# DRV10975_3-ph_Sensorless_BLDC_Motor_Driv.net
KiCad netlist of a schematic drawn in Altium Designer
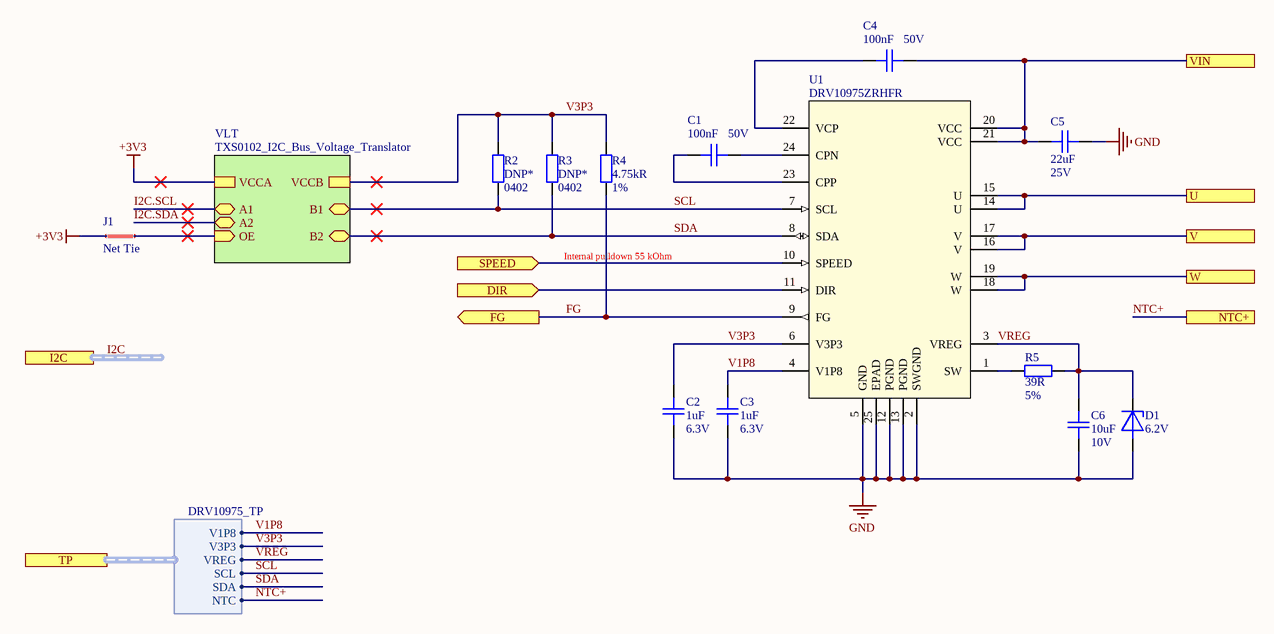
[diagram p0: DRV10975 3-ph Sensorless BLDC Motor Driver.SchDoc]

(export (version "E")
  (design (tool "Eeschema 10.0.6"))
  (components
    (comp (ref "C1")
      (value "CAP CER 0.1UF 50V X7R 0402")
      (footprint "C0402")
      (description "0.1µF ±10% 50V Ceramic Capacitor X7R 0402 (1005 Metric)")
      (fields
        (field (name "MANUFACTURER") "TDK")
        (field (name "MANUFACTURER PART NUMBER") "CGA2B3X7R1H104K050BB")
        (field (name "CAPACITANCE") "100nF")
        (field (name "VOLTAGE") "50V")
      )
      (libsource (lib "capacitors_smd") (part "CAP CER 0.1UF 50V X7R 0402"))
    )
    (comp (ref "C2")
      (value "CAP CER 1UF 6.3V X5R 0402")
      (footprint "C0402")
      (description "1µF ±10% 6.3V Ceramic Capacitor X5R 0402 (1005 Metric)")
      (fields
        (field (name "MANUFACTURER") "Yageo")
        (field (name "MANUFACTURER PART NUMBER") "CC0402KRX5R5BB105")
        (field (name "CAPACITANCE") "1uF")
        (field (name "VOLTAGE RATING") "6.3V")
      )
      (libsource (lib "capacitors_smd") (part "CAP CER 1UF 6.3V X5R 0402"))
    )
    (comp (ref "C3")
      (value "CAP CER 1UF 6.3V X5R 0402")
      (footprint "C0402")
      (description "1µF ±10% 6.3V Ceramic Capacitor X5R 0402 (1005 Metric)")
      (fields
        (field (name "MANUFACTURER") "Yageo")
        (field (name "MANUFACTURER PART NUMBER") "CC0402KRX5R5BB105")
        (field (name "CAPACITANCE") "1uF")
        (field (name "VOLTAGE RATING") "6.3V")
      )
      (libsource (lib "capacitors_smd") (part "CAP CER 1UF 6.3V X5R 0402"))
    )
    (comp (ref "C4")
      (value "CAP CER 0.1UF 50V X7R 0402")
      (footprint "C0402")
      (description "0.1µF ±10% 50V Ceramic Capacitor X7R 0402 (1005 Metric)")
      (fields
        (field (name "MANUFACTURER") "TDK")
        (field (name "MANUFACTURER PART NUMBER") "CGA2B3X7R1H104K050BB")
        (field (name "CAPACITANCE") "100nF")
        (field (name "VOLTAGE") "50V")
      )
      (libsource (lib "capacitors_smd") (part "CAP CER 0.1UF 50V X7R 0402"))
    )
    (comp (ref "C5")
      (value "CAP CER 22UF 25V X5R 0805")
      (footprint "C0805")
      (description "22µF ±20% 25V Ceramic Capacitor X5R 0805 (2012 Metric)")
      (fields
        (field (name "MANUFACTURER") "Yageo")
        (field (name "MANUFACTURER PART NUMBER") "CC0805MKX5R8BB226")
        (field (name "CAPACITANCE") "22uF")
        (field (name "VOLTAGE RATING") "25V")
      )
      (libsource (lib "capacitors_smd") (part "CAP CER 22UF 25V X5R 0805"))
    )
    (comp (ref "C6")
      (value "CAP CER 10uF X7R 10% 0805")
      (footprint "C0805")
      (description "Capacitor,10uF,10V,X7R,10%,0805,Murata")
      (fields
        (field (name "MANUFACTURER") "Murata")
        (field (name "MANUFACTURER PART NUMBER") "GRM21BR71A106KA73L")
        (field (name "CAPACITANCE") "10uF")
        (field (name "VOLTAGE RATING") "10V")
      )
      (libsource (lib "capacitors_smd") (part "CAP CER 10uF X7R 10% 0805"))
    )
    (comp (ref "D1")
      (value "Zener Diode 6.2V 2.5W ±5% Surface Mount SOD-123FL")
      (footprint "SOD-123FL")
      (fields
        (field (name "MANUFACTURER") "ON Semiconductor")
        (field (name "MANUFACTURER PART NUMBER") "1SMF5920BT1G")
        (field (name "TOLERANCE") "5%")
        (field (name "ZENER VOLTAGE") "6.2V")
      )
      (libsource (lib "diodes_zener") (part "DIODE ZENER 6.2V 2.5W SOD123FL"))
    )
    (comp (ref "J1")
      (value "Net Tie")
      (footprint "Net Tie 6x30mil")
      (libsource (lib "BLDC_Motor_Driver") (part "Net Tie Line"))
    )
    (comp (ref "R2")
      (value "DNP*")
      (footprint "R0402")
      (description "Placeholder for a 0402 resistor")
      (fields (field (name "CASE/PACKAGE") "0402"))
      (libsource (lib "resistors_smd") (part "RES SMD NO BOM 0402"))
    )
    (comp (ref "R3")
      (value "DNP*")
      (footprint "R0402")
      (description "Placeholder for a 0402 resistor")
      (fields (field (name "CASE/PACKAGE") "0402"))
      (libsource (lib "resistors_smd") (part "RES SMD NO BOM 0402"))
    )
    (comp (ref "R4")
      (value "RES SMD 4.75K OHM 1% 1/16W 0402")
      (footprint "R0402")
      (description "4.75 kOhms ±1% 0.063W, 1/16W Chip Resistor 0402 (1005 Metric) Moisture Resistant Thick Film")
      (fields
        (field (name "MANUFACTURER") "Yageo")
        (field (name "MANUFACTURER PART NUMBER") "RC0402FR-074K75P")
        (field (name "RESISTANCE") "4.75kR")
        (field (name "TOLERANCE") "1%")
      )
      (libsource (lib "resistors_smd") (part "RES SMD 4.75K OHM 1% 1/16W 0402"))
    )
    (comp (ref "R5")
      (value "RES SMD 39 OHM 1% 1/4W 1206")
      (footprint "R1206")
      (description "39 Ohms ±5% 0.25W, 1/4W Chip Resistor 1206 (3216 Metric) Moisture Resistant Thick Film")
      (fields
        (field (name "MANUFACTURER") "Yageo")
        (field (name "MANUFACTURER PART NUMBER") "RC1206JR-0739RL")
        (field (name "RESISTANCE") "39R")
        (field (name "TOLERANCE") "5%")
      )
      (libsource (lib "resistors_smd") (part "RES SMD 39 OHM 1% 1/4W 1206"))
    )
    (comp (ref "U1")
      (value "DRV10975ZRHFR")
      (footprint "RHF24_2P65X3P65")
      (description "Multiphase Motor Driver Power MOSFET Analog, I²C, PWM 24-VQFN (5x4)")
      (fields (field (name "MANUFACTURER") "Texas Instruments"))
      (libsource (lib "BLDC_Moto_Driver") (part "IC DRV10975Z BLDC MOTOR DRIVER VQFN-24"))
    )
  )
  (nets
    (net (code "3") (name "+3V3") (class "Default") (node (ref "J1") (pin "1") (pintype "passive")))
    (net (code "4") (name "/DIR") (class "Default")
      (node (ref "U1") (pin "11") (pinfunction "DIR_11") (pintype "input"))
    )
    (net (code "5") (name "/FG") (class "Default")
      (node (ref "R4") (pin "2") (pinfunction "2_2") (pintype "passive"))
      (node (ref "U1") (pin "9") (pinfunction "FG_9") (pintype "output"))
    )
    (net (code "9") (name "/OE") (class "Default") (node (ref "J1") (pin "2") (pintype "passive")))
    (net (code "10") (name "/SCL") (class "Default")
      (node (ref "R2") (pin "1") (pinfunction "1_1") (pintype "passive"))
      (node (ref "U1") (pin "7") (pinfunction "SCL_7") (pintype "input"))
    )
    (net (code "11") (name "/SDA") (class "Default")
      (node (ref "R3") (pin "1") (pinfunction "1_1") (pintype "passive"))
      (node (ref "U1") (pin "8") (pinfunction "SDA_8") (pintype "bidirectional"))
    )
    (net (code "12") (name "/SPEED") (class "Default")
      (node (ref "U1") (pin "10") (pinfunction "SPEED_10") (pintype "input"))
    )
    (net (code "13") (name "/U") (class "Default")
      (node (ref "U1") (pin "14") (pinfunction "U_14") (pintype "power_in"))
      (node (ref "U1") (pin "15") (pinfunction "U_15") (pintype "power_in"))
    )
    (net (code "14") (name "/V") (class "Default")
      (node (ref "U1") (pin "16") (pinfunction "V_16") (pintype "power_in"))
      (node (ref "U1") (pin "17") (pinfunction "V_17") (pintype "power_in"))
    )
    (net (code "15") (name "/V1P8") (class "Default")
      (node (ref "C3") (pin "2") (pinfunction "2_2") (pintype "passive"))
      (node (ref "U1") (pin "4") (pinfunction "V1P8_4") (pintype "power_in"))
    )
    (net (code "16") (name "/V3P3") (class "Default")
      (node (ref "C2") (pin "2") (pinfunction "2_2") (pintype "passive"))
      (node (ref "R2") (pin "2") (pinfunction "2_2") (pintype "passive"))
      (node (ref "R3") (pin "2") (pinfunction "2_2") (pintype "passive"))
      (node (ref "R4") (pin "1") (pinfunction "1_1") (pintype "passive"))
      (node (ref "U1") (pin "6") (pinfunction "V3P3_6") (pintype "power_in"))
    )
    (net (code "17") (name "/VIN") (class "Default")
      (node (ref "C4") (pin "2") (pinfunction "2_2") (pintype "passive"))
      (node (ref "C5") (pin "1") (pinfunction "1_1") (pintype "passive"))
      (node (ref "U1") (pin "20") (pinfunction "VCC_20") (pintype "power_in"))
      (node (ref "U1") (pin "21") (pinfunction "VCC_21") (pintype "power_in"))
    )
    (net (code "18") (name "/VREG") (class "Default")
      (node (ref "C6") (pin "1") (pinfunction "1_1") (pintype "passive"))
      (node (ref "D1") (pin "1") (pinfunction "K_1") (pintype "passive"))
      (node (ref "R5") (pin "2") (pinfunction "2_2") (pintype "passive"))
      (node (ref "U1") (pin "3") (pinfunction "VREG_3") (pintype "power_in"))
    )
    (net (code "19") (name "/W") (class "Default")
      (node (ref "U1") (pin "18") (pinfunction "W_18") (pintype "power_in"))
      (node (ref "U1") (pin "19") (pinfunction "W_19") (pintype "power_in"))
    )
    (net (code "22") (name "GND") (class "Default")
      (node (ref "C2") (pin "1") (pinfunction "1_1") (pintype "passive"))
      (node (ref "C3") (pin "1") (pinfunction "1_1") (pintype "passive"))
      (node (ref "C5") (pin "2") (pinfunction "2_2") (pintype "passive"))
      (node (ref "C6") (pin "2") (pinfunction "2_2") (pintype "passive"))
      (node (ref "D1") (pin "2") (pinfunction "A_2") (pintype "passive"))
      (node (ref "U1") (pin "12") (pinfunction "PGND_12") (pintype "power_in"))
      (node (ref "U1") (pin "13") (pinfunction "PGND_13") (pintype "power_in"))
      (node (ref "U1") (pin "2") (pinfunction "SWGND_2") (pintype "power_in"))
      (node (ref "U1") (pin "25") (pinfunction "EPAD_25") (pintype "power_in"))
      (node (ref "U1") (pin "5") (pinfunction "GND_5") (pintype "power_in"))
    )
    (net (code "23") (name "Net-(U1-CPN)") (class "Default")
      (node (ref "C1") (pin "2") (pinfunction "2_2") (pintype "passive"))
      (node (ref "U1") (pin "24") (pinfunction "CPN_24") (pintype "power_in"))
    )
    (net (code "24") (name "Net-(U1-CPP)") (class "Default")
      (node (ref "C1") (pin "1") (pinfunction "1_1") (pintype "passive"))
      (node (ref "U1") (pin "23") (pinfunction "CPP_23") (pintype "power_in"))
    )
    (net (code "25") (name "Net-(U1-SW)") (class "Default")
      (node (ref "R5") (pin "1") (pinfunction "1_1") (pintype "passive"))
      (node (ref "U1") (pin "1") (pinfunction "SW_1") (pintype "power_in"))
    )
    (net (code "26") (name "Net-(U1-VCP)") (class "Default")
      (node (ref "C4") (pin "1") (pinfunction "1_1") (pintype "passive"))
      (node (ref "U1") (pin "22") (pinfunction "VCP_22") (pintype "power_in"))
    )
  )
)
